# power_supply.net
KiCad netlist of a schematic drawn in EAGLE
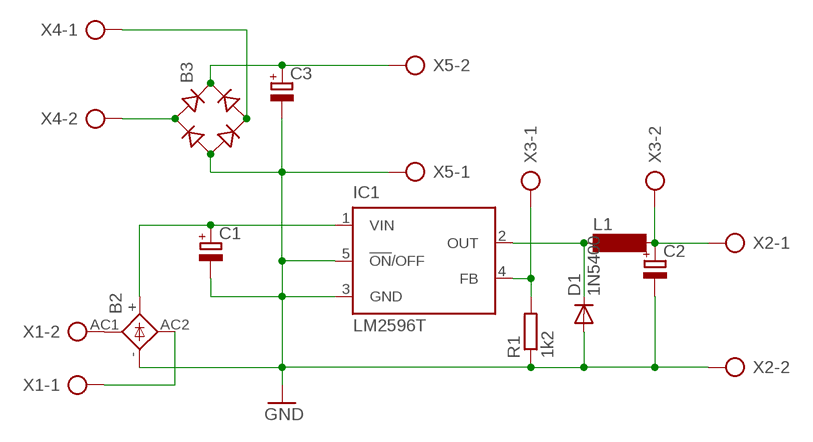
[diagram p0: schematic, sheet 1]

(export (version "E")
  (design (tool "Eeschema 10.0.6"))
  (components
    (comp (ref "B2")
      (value "FB15")
      (footprint "eagle-import:FB15")
      (libsource (lib "eagle-import") (part "FB15"))
    )
    (comp (ref "B3")
      (value "B-DIL")
      (footprint "eagle-import:B-DIL")
      (libsource (lib "eagle-import") (part "B-DIL"))
    )
    (comp (ref "C1")
      (value "CPOL-EUTT5D11")
      (footprint "eagle-import:TT5D11")
      (libsource (lib "eagle-import") (part "CPOL-EUTT5D11"))
    )
    (comp (ref "C2")
      (value "CPOL-EUTT5D11")
      (footprint "eagle-import:TT5D11")
      (libsource (lib "eagle-import") (part "CPOL-EUTT5D11"))
    )
    (comp (ref "C3")
      (value "CPOL-EUTT5D11")
      (footprint "eagle-import:TT5D11")
      (libsource (lib "eagle-import") (part "CPOL-EUTT5D11"))
    )
    (comp (ref "D1")
      (value "1N5400")
      (footprint "eagle-import:DO201-15")
      (libsource (lib "eagle-import") (part "1N5400"))
    )
    (comp (ref "IC1")
      (value "LM2596T")
      (footprint "eagle-import:T05D")
      (fields (field (name "MPN") "LM2596T-ADJ/LF02"))
      (libsource (lib "eagle-import") (part "LM2596T"))
    )
    (comp (ref "L1")
      (value "SD12K-82")
      (footprint "eagle-import:SD12K-82")
      (libsource (lib "eagle-import") (part "SD12K-82"))
    )
    (comp (ref "R1")
      (value "1k2")
      (footprint "eagle-import:0207_10")
      (libsource (lib "eagle-import") (part "R-EU_0207/10"))
    )
    (comp (ref "X1")
      (value "AK300/2")
      (footprint "eagle-import:AK300_2")
      (libsource (lib "eagle-import") (part "AK300/2"))
    )
    (comp (ref "X2")
      (value "AK300/2")
      (footprint "eagle-import:AK300_2")
      (libsource (lib "eagle-import") (part "AK300/2"))
    )
    (comp (ref "X3")
      (value "AK300/2")
      (footprint "eagle-import:AK300_2")
      (fields (field (name "OC_FARNELL") "unknown") (field (name "OC_NEWARK") "unknown"))
      (libsource (lib "eagle-import") (part "AK300/2"))
    )
    (comp (ref "X4")
      (value "AK300/2")
      (footprint "eagle-import:AK300_2")
      (fields (field (name "OC_FARNELL") "unknown") (field (name "OC_NEWARK") "unknown"))
      (libsource (lib "eagle-import") (part "AK300/2"))
    )
    (comp (ref "X5")
      (value "AK300/2")
      (footprint "eagle-import:AK300_2")
      (fields (field (name "OC_FARNELL") "unknown") (field (name "OC_NEWARK") "unknown"))
      (libsource (lib "eagle-import") (part "AK300/2"))
    )
  )
  (nets
    (net (code "1") (name "GND") (class "Default")
      (node (ref "B2") (pin "-") (pinfunction "-_-") (pintype "passive"))
      (node (ref "B3") (pin "-") (pinfunction "-_-") (pintype "passive"))
      (node (ref "C1") (pin "-") (pinfunction "-_-") (pintype "passive"))
      (node (ref "C2") (pin "-") (pinfunction "-_-") (pintype "passive"))
      (node (ref "C3") (pin "-") (pinfunction "-_-") (pintype "passive"))
      (node (ref "D1") (pin "A") (pinfunction "A_A") (pintype "passive"))
      (node (ref "IC1") (pin "3") (pinfunction "GND_3") (pintype "power_in"))
      (node (ref "IC1") (pin "5") (pinfunction "~{ON}/OFF_5") (pintype "input"))
      (node (ref "R1") (pin "1") (pinfunction "1_1") (pintype "passive"))
      (node (ref "X2") (pin "2") (pinfunction "KL_2") (pintype "passive"))
      (node (ref "X5") (pin "1") (pinfunction "KL_1") (pintype "passive"))
    )
    (net (code "2") (name "Net-(IC1-FB)") (class "Default")
      (node (ref "IC1") (pin "4") (pinfunction "FB_4") (pintype "input"))
      (node (ref "R1") (pin "2") (pinfunction "2_2") (pintype "passive"))
      (node (ref "X3") (pin "1") (pinfunction "KL_1") (pintype "passive"))
    )
    (net (code "3") (name "Net-(IC1-OUT)") (class "Default")
      (node (ref "D1") (pin "C") (pinfunction "C_C") (pintype "passive"))
      (node (ref "IC1") (pin "2") (pinfunction "OUT_2") (pintype "output"))
      (node (ref "L1") (pin "1") (pinfunction "1_1") (pintype "passive"))
    )
    (net (code "4") (name "Net-(IC1-VIN)") (class "Default")
      (node (ref "B2") (pin "+") (pinfunction "+_+") (pintype "passive"))
      (node (ref "C1") (pin "+") (pinfunction "+_+") (pintype "passive"))
      (node (ref "IC1") (pin "1") (pinfunction "VIN_1") (pintype "input"))
    )
    (net (code "5") (name "Net-(X1A-KL)") (class "Default")
      (node (ref "B2") (pin "AC2") (pinfunction "AC2_AC2") (pintype "passive"))
      (node (ref "X1") (pin "1") (pinfunction "KL_1") (pintype "passive"))
    )
    (net (code "6") (name "Net-(X1B-KL)") (class "Default")
      (node (ref "B2") (pin "AC1") (pinfunction "AC1_AC1") (pintype "passive"))
      (node (ref "X1") (pin "2") (pinfunction "KL_2") (pintype "passive"))
    )
    (net (code "7") (name "Net-(X2A-KL)") (class "Default")
      (node (ref "C2") (pin "+") (pinfunction "+_+") (pintype "passive"))
      (node (ref "L1") (pin "2") (pinfunction "2_2") (pintype "passive"))
      (node (ref "X2") (pin "1") (pinfunction "KL_1") (pintype "passive"))
      (node (ref "X3") (pin "2") (pinfunction "KL_2") (pintype "passive"))
    )
    (net (code "8") (name "Net-(X4A-KL)") (class "Default")
      (node (ref "B3") (pin "AC2") (pinfunction "AC2_AC2") (pintype "passive"))
      (node (ref "X4") (pin "1") (pinfunction "KL_1") (pintype "passive"))
    )
    (net (code "9") (name "Net-(X4B-KL)") (class "Default")
      (node (ref "B3") (pin "AC1") (pinfunction "AC1_AC1") (pintype "passive"))
      (node (ref "X4") (pin "2") (pinfunction "KL_2") (pintype "passive"))
    )
    (net (code "10") (name "Net-(X5B-KL)") (class "Default")
      (node (ref "B3") (pin "+") (pinfunction "+_+") (pintype "passive"))
      (node (ref "C3") (pin "+") (pinfunction "+_+") (pintype "passive"))
      (node (ref "X5") (pin "2") (pinfunction "KL_2") (pintype "passive"))
    )
  )
)
